# balancing_bot_shield.net
KiCad netlist of a schematic drawn in EAGLE
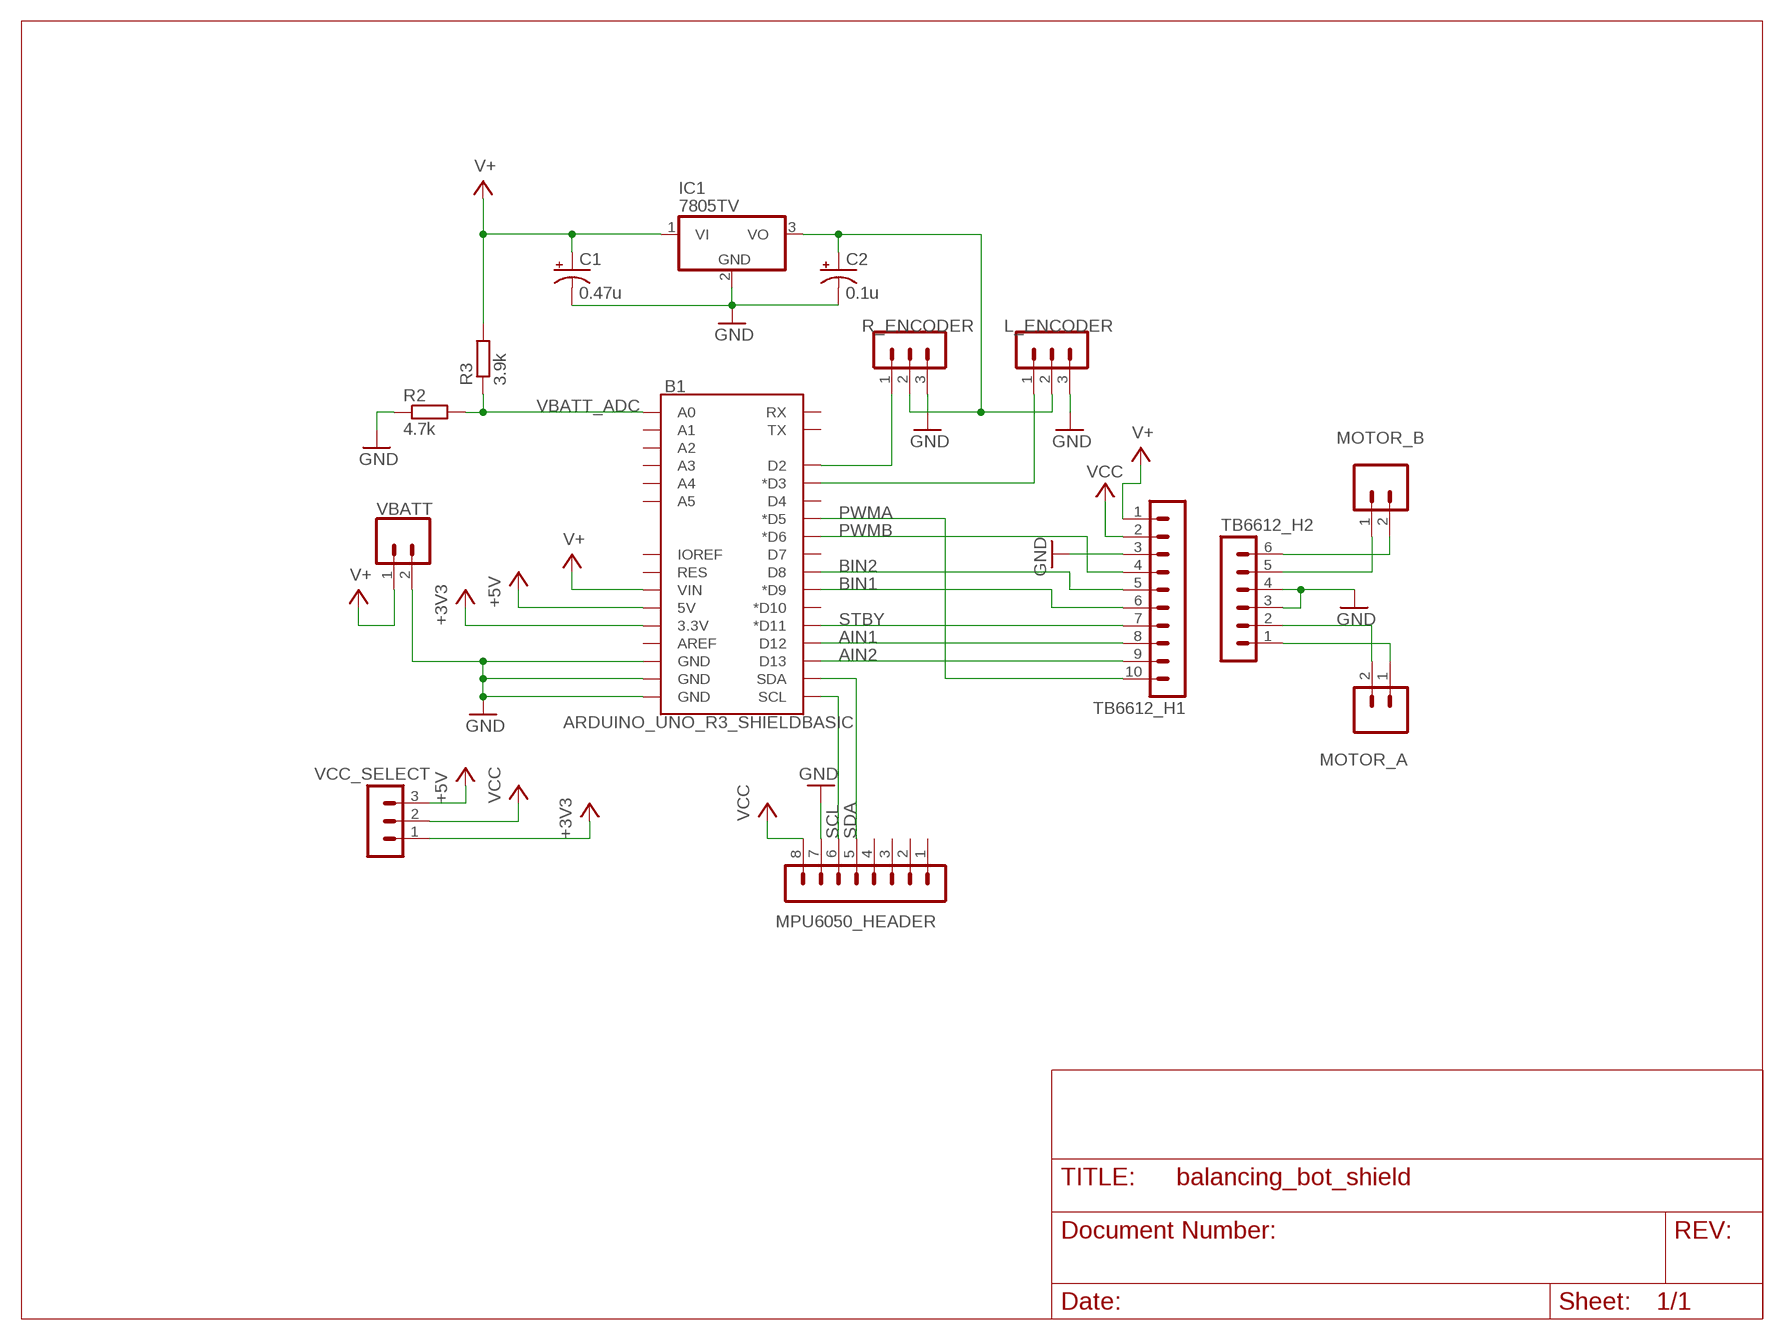
[diagram p0: schematic, sheet 1]

(export (version "E")
  (design (tool "Eeschema 10.0.6"))
  (components
    (comp (ref "B1")
      (value "ARDUINO_UNO_R3_SHIELDBASIC")
      (footprint "eagle-import:UNO_R3_SHIELD")
      (libsource (lib "eagle-import") (part "ARDUINO_UNO_R3_SHIELDBASIC"))
    )
    (comp (ref "C1")
      (value "0.47u")
      (footprint "eagle-import:E5-5")
      (libsource (lib "eagle-import") (part "CPOL-USE5-5"))
    )
    (comp (ref "C2")
      (value "0.1u")
      (footprint "eagle-import:E5-5")
      (libsource (lib "eagle-import") (part "CPOL-USE5-5"))
    )
    (comp (ref "IC1")
      (value "7805TV")
      (footprint "eagle-import:TO220V")
      (libsource (lib "eagle-import") (part "78TV05"))
    )
    (comp (ref "L_ENCODER")
      (value "MA03-1")
      (footprint "eagle-import:MA03-1")
      (libsource (lib "eagle-import") (part "MA03-1"))
    )
    (comp (ref "MOTOR_A")
      (value "CONN_025MM")
      (footprint "eagle-import:SCREWTERMINAL-5MM-2")
      (libsource (lib "eagle-import") (part "CONN_025MM"))
    )
    (comp (ref "MOTOR_B")
      (value "CONN_025MM")
      (footprint "eagle-import:SCREWTERMINAL-5MM-2")
      (libsource (lib "eagle-import") (part "CONN_025MM"))
    )
    (comp (ref "MPU6050_HEADER")
      (value "MA08-1")
      (footprint "eagle-import:MA08-1")
      (libsource (lib "eagle-import") (part "MA08-1"))
    )
    (comp (ref "R2")
      (value "4.7k")
      (footprint "eagle-import:0207_10")
      (libsource (lib "eagle-import") (part "R-EU_0207/10"))
    )
    (comp (ref "R3")
      (value "3.9k")
      (footprint "eagle-import:0207_10")
      (libsource (lib "eagle-import") (part "R-EU_0207/10"))
    )
    (comp (ref "R_ENCODER")
      (value "MA03-1")
      (footprint "eagle-import:MA03-1")
      (libsource (lib "eagle-import") (part "MA03-1"))
    )
    (comp (ref "TB6612_H1")
      (value "MA10-1")
      (footprint "eagle-import:MA10-1")
      (libsource (lib "eagle-import") (part "MA10-1"))
    )
    (comp (ref "TB6612_H2")
      (value "MA06-1")
      (footprint "eagle-import:MA06-1")
      (libsource (lib "eagle-import") (part "MA06-1"))
    )
    (comp (ref "VBATT")
      (value "CONN_025MM")
      (footprint "eagle-import:SCREWTERMINAL-5MM-2")
      (libsource (lib "eagle-import") (part "CONN_025MM"))
    )
    (comp (ref "VCC_SELECT")
      (value "MA03-1")
      (footprint "eagle-import:MA03-1")
      (libsource (lib "eagle-import") (part "MA03-1"))
    )
  )
  (nets
    (net (code "1") (name "+3V3") (class "Default")
      (node (ref "B1") (pin "3.3V") (pinfunction "3.3V_3.3V") (pintype "bidirectional"))
      (node (ref "VCC_SELECT") (pin "1") (pinfunction "1_1") (pintype "passive"))
    )
    (net (code "2") (name "+5V") (class "Default")
      (node (ref "B1") (pin "5V") (pinfunction "5V_5V") (pintype "bidirectional"))
      (node (ref "VCC_SELECT") (pin "3") (pinfunction "3_3") (pintype "passive"))
    )
    (net (code "3") (name "/AIN1") (class "Default")
      (node (ref "B1") (pin "D12") (pinfunction "D12_D12") (pintype "bidirectional"))
      (node (ref "TB6612_H1") (pin "8") (pinfunction "8_8") (pintype "passive"))
    )
    (net (code "4") (name "/AIN2") (class "Default")
      (node (ref "B1") (pin "D13") (pinfunction "D13_D13") (pintype "bidirectional"))
      (node (ref "TB6612_H1") (pin "9") (pinfunction "9_9") (pintype "passive"))
    )
    (net (code "5") (name "/BIN1") (class "Default")
      (node (ref "B1") (pin "D9") (pinfunction "*D9_D9") (pintype "bidirectional"))
      (node (ref "TB6612_H1") (pin "6") (pinfunction "6_6") (pintype "passive"))
    )
    (net (code "6") (name "/BIN2") (class "Default")
      (node (ref "B1") (pin "D8") (pinfunction "D8_D8") (pintype "bidirectional"))
      (node (ref "TB6612_H1") (pin "5") (pinfunction "5_5") (pintype "passive"))
    )
    (net (code "7") (name "/PWMA") (class "Default")
      (node (ref "B1") (pin "D5") (pinfunction "*D5_D5") (pintype "bidirectional"))
      (node (ref "TB6612_H1") (pin "10") (pinfunction "10_10") (pintype "passive"))
    )
    (net (code "8") (name "/PWMB") (class "Default")
      (node (ref "B1") (pin "D6") (pinfunction "*D6_D6") (pintype "bidirectional"))
      (node (ref "TB6612_H1") (pin "4") (pinfunction "4_4") (pintype "passive"))
    )
    (net (code "9") (name "/SCL") (class "Default")
      (node (ref "B1") (pin "SCL") (pinfunction "SCL_SCL") (pintype "bidirectional"))
      (node (ref "MPU6050_HEADER") (pin "6") (pinfunction "6_6") (pintype "passive"))
    )
    (net (code "10") (name "/SDA") (class "Default")
      (node (ref "B1") (pin "SDA") (pinfunction "SDA_SDA") (pintype "bidirectional"))
      (node (ref "MPU6050_HEADER") (pin "5") (pinfunction "5_5") (pintype "passive"))
    )
    (net (code "11") (name "/STBY") (class "Default")
      (node (ref "B1") (pin "D11") (pinfunction "*D11_D11") (pintype "bidirectional"))
      (node (ref "TB6612_H1") (pin "7") (pinfunction "7_7") (pintype "passive"))
    )
    (net (code "12") (name "/VBATT_ADC") (class "Default")
      (node (ref "B1") (pin "A0") (pinfunction "A0_A0") (pintype "bidirectional"))
      (node (ref "R2") (pin "2") (pinfunction "2_2") (pintype "passive"))
      (node (ref "R3") (pin "1") (pinfunction "1_1") (pintype "passive"))
    )
    (net (code "13") (name "GND") (class "Default")
      (node (ref "B1") (pin "GND@0") (pinfunction "GND_GND@0") (pintype "bidirectional"))
      (node (ref "B1") (pin "GND@1") (pinfunction "GND_GND@1") (pintype "bidirectional"))
      (node (ref "B1") (pin "GND@2") (pinfunction "GND_GND@2") (pintype "bidirectional"))
      (node (ref "C1") (pin "-") (pinfunction "-_-") (pintype "passive"))
      (node (ref "C2") (pin "-") (pinfunction "-_-") (pintype "passive"))
      (node (ref "IC1") (pin "2") (pinfunction "GND_2") (pintype "passive"))
      (node (ref "L_ENCODER") (pin "3") (pinfunction "3_3") (pintype "passive"))
      (node (ref "MPU6050_HEADER") (pin "7") (pinfunction "7_7") (pintype "passive"))
      (node (ref "R2") (pin "1") (pinfunction "1_1") (pintype "passive"))
      (node (ref "R_ENCODER") (pin "3") (pinfunction "3_3") (pintype "passive"))
      (node (ref "TB6612_H1") (pin "3") (pinfunction "3_3") (pintype "passive"))
      (node (ref "TB6612_H2") (pin "3") (pinfunction "3_3") (pintype "passive"))
      (node (ref "TB6612_H2") (pin "4") (pinfunction "4_4") (pintype "passive"))
      (node (ref "VBATT") (pin "2") (pinfunction "2_2") (pintype "passive"))
    )
    (net (code "14") (name "Net-(B1-*D3)") (class "Default")
      (node (ref "B1") (pin "D3") (pinfunction "*D3_D3") (pintype "bidirectional"))
      (node (ref "L_ENCODER") (pin "1") (pinfunction "1_1") (pintype "passive"))
    )
    (net (code "15") (name "Net-(B1-PadD2)") (class "Default")
      (node (ref "B1") (pin "D2") (pinfunction "D2_D2") (pintype "bidirectional"))
      (node (ref "R_ENCODER") (pin "1") (pinfunction "1_1") (pintype "passive"))
    )
    (net (code "16") (name "Net-(IC1-VO)") (class "Default")
      (node (ref "C2") (pin "+") (pinfunction "+_+") (pintype "passive"))
      (node (ref "IC1") (pin "3") (pinfunction "VO_3") (pintype "passive"))
      (node (ref "L_ENCODER") (pin "2") (pinfunction "2_2") (pintype "passive"))
      (node (ref "R_ENCODER") (pin "2") (pinfunction "2_2") (pintype "passive"))
    )
    (net (code "17") (name "Net-(MOTOR_A-Pad1)") (class "Default")
      (node (ref "MOTOR_A") (pin "1") (pinfunction "1_1") (pintype "passive"))
      (node (ref "TB6612_H2") (pin "1") (pinfunction "1_1") (pintype "passive"))
    )
    (net (code "18") (name "Net-(MOTOR_A-Pad2)") (class "Default")
      (node (ref "MOTOR_A") (pin "2") (pinfunction "2_2") (pintype "passive"))
      (node (ref "TB6612_H2") (pin "2") (pinfunction "2_2") (pintype "passive"))
    )
    (net (code "19") (name "Net-(MOTOR_B-Pad1)") (class "Default")
      (node (ref "MOTOR_B") (pin "1") (pinfunction "1_1") (pintype "passive"))
      (node (ref "TB6612_H2") (pin "5") (pinfunction "5_5") (pintype "passive"))
    )
    (net (code "20") (name "Net-(MOTOR_B-Pad2)") (class "Default")
      (node (ref "MOTOR_B") (pin "2") (pinfunction "2_2") (pintype "passive"))
      (node (ref "TB6612_H2") (pin "6") (pinfunction "6_6") (pintype "passive"))
    )
    (net (code "21") (name "V+") (class "Default")
      (node (ref "B1") (pin "VIN") (pinfunction "VIN_VIN") (pintype "bidirectional"))
      (node (ref "C1") (pin "+") (pinfunction "+_+") (pintype "passive"))
      (node (ref "IC1") (pin "1") (pinfunction "VI_1") (pintype "input"))
      (node (ref "R3") (pin "2") (pinfunction "2_2") (pintype "passive"))
      (node (ref "TB6612_H1") (pin "1") (pinfunction "1_1") (pintype "passive"))
      (node (ref "VBATT") (pin "1") (pinfunction "1_1") (pintype "passive"))
    )
    (net (code "22") (name "VCC") (class "Default")
      (node (ref "MPU6050_HEADER") (pin "8") (pinfunction "8_8") (pintype "passive"))
      (node (ref "TB6612_H1") (pin "2") (pinfunction "2_2") (pintype "passive"))
      (node (ref "VCC_SELECT") (pin "2") (pinfunction "2_2") (pintype "passive"))
    )
    (net (code "23") (name "unconnected-(B1-*D10-PadD10)") (class "Default")
      (node (ref "B1") (pin "D10") (pinfunction "*D10_D10") (pintype "bidirectional"))
    )
    (net (code "24") (name "unconnected-(B1-PadA1)") (class "Default")
      (node (ref "B1") (pin "A1") (pinfunction "A1_A1") (pintype "bidirectional"))
    )
    (net (code "25") (name "unconnected-(B1-PadA2)") (class "Default")
      (node (ref "B1") (pin "A2") (pinfunction "A2_A2") (pintype "bidirectional"))
    )
    (net (code "26") (name "unconnected-(B1-PadA3)") (class "Default")
      (node (ref "B1") (pin "A3") (pinfunction "A3_A3") (pintype "bidirectional"))
    )
    (net (code "27") (name "unconnected-(B1-PadA4)") (class "Default")
      (node (ref "B1") (pin "A4") (pinfunction "A4_A4") (pintype "bidirectional"))
    )
    (net (code "28") (name "unconnected-(B1-PadA5)") (class "Default")
      (node (ref "B1") (pin "A5") (pinfunction "A5_A5") (pintype "bidirectional"))
    )
    (net (code "29") (name "unconnected-(B1-PadAREF)") (class "Default")
      (node (ref "B1") (pin "AREF") (pinfunction "AREF_AREF") (pintype "bidirectional"))
    )
    (net (code "30") (name "unconnected-(B1-PadD4)") (class "Default")
      (node (ref "B1") (pin "D4") (pinfunction "D4_D4") (pintype "bidirectional"))
    )
    (net (code "31") (name "unconnected-(B1-PadD7)") (class "Default")
      (node (ref "B1") (pin "D7") (pinfunction "D7_D7") (pintype "bidirectional"))
    )
    (net (code "32") (name "unconnected-(B1-PadIOREF)") (class "Default")
      (node (ref "B1") (pin "IOREF") (pinfunction "IOREF_IOREF") (pintype "bidirectional"))
    )
    (net (code "33") (name "unconnected-(B1-PadRES)") (class "Default")
      (node (ref "B1") (pin "RES") (pinfunction "RES_RES") (pintype "bidirectional"))
    )
    (net (code "34") (name "unconnected-(B1-PadRX)") (class "Default")
      (node (ref "B1") (pin "RX") (pinfunction "RX_RX") (pintype "bidirectional"))
    )
    (net (code "35") (name "unconnected-(B1-PadTX)") (class "Default")
      (node (ref "B1") (pin "TX") (pinfunction "TX_TX") (pintype "bidirectional"))
    )
    (net (code "36") (name "unconnected-(MPU6050_HEADER-Pad1)") (class "Default")
      (node (ref "MPU6050_HEADER") (pin "1") (pinfunction "1_1") (pintype "passive"))
    )
    (net (code "37") (name "unconnected-(MPU6050_HEADER-Pad2)") (class "Default")
      (node (ref "MPU6050_HEADER") (pin "2") (pinfunction "2_2") (pintype "passive"))
    )
    (net (code "38") (name "unconnected-(MPU6050_HEADER-Pad3)") (class "Default")
      (node (ref "MPU6050_HEADER") (pin "3") (pinfunction "3_3") (pintype "passive"))
    )
    (net (code "39") (name "unconnected-(MPU6050_HEADER-Pad4)") (class "Default")
      (node (ref "MPU6050_HEADER") (pin "4") (pinfunction "4_4") (pintype "passive"))
    )
  )
)
